# leanometer.net
KiCad netlist of a schematic drawn in EAGLE
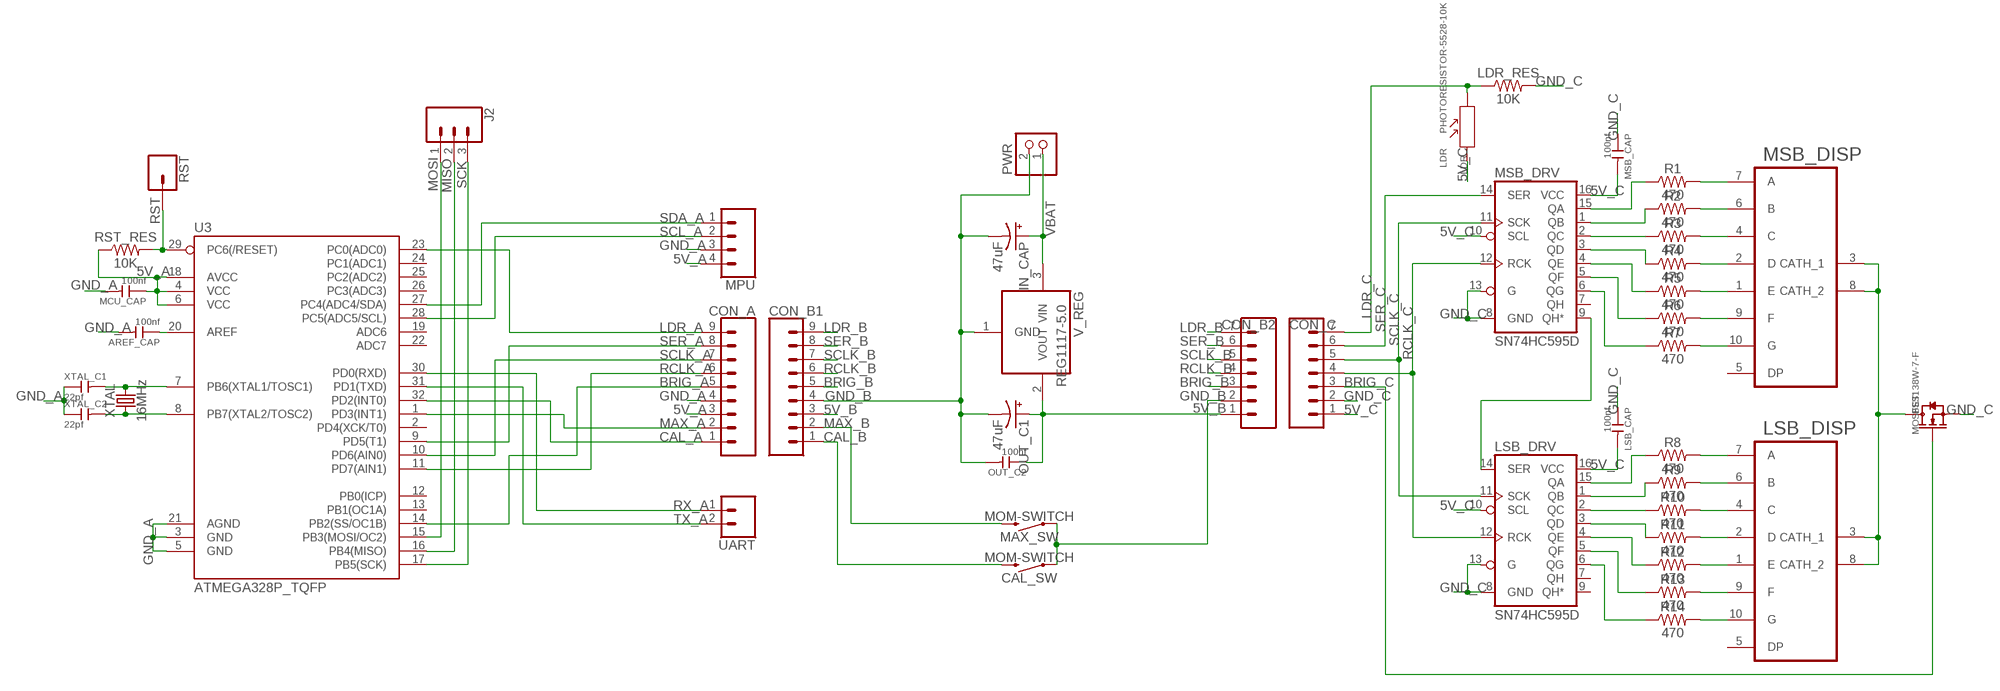
[diagram p0: schematic, sheet 1]

(export (version "E")
  (design (tool "Eeschema 10.0.6"))
  (components
    (comp (ref "AREF_CAP")
      (value "100nf")
      (footprint "eagle-import:C0805")
      (fields (field (name "MPN") "CC0805KRX7R9BB104"))
      (libsource (lib "eagle-import") (part "CERAMIC-100NF-50V-10%-X7R(0805)"))
    )
    (comp (ref "CAL_SW")
      (value "MOM-SWITCH")
      (footprint "eagle-import:TACTILE_SWITCH_PTH_6.0MM")
      (libsource (lib "eagle-import") (part "MOMENTARY-SWITCH-SPST-PTH-6.0MM"))
    )
    (comp (ref "CON_A")
      (value "CONN_09")
      (footprint "eagle-import:1X09")
      (libsource (lib "eagle-import") (part "CONN_09"))
    )
    (comp (ref "CON_B1")
      (value "CONN_09")
      (footprint "eagle-import:1X09")
      (libsource (lib "eagle-import") (part "CONN_09"))
    )
    (comp (ref "CON_B2")
      (value "CONN_07")
      (footprint "eagle-import:1X07")
      (libsource (lib "eagle-import") (part "CONN_07"))
    )
    (comp (ref "CON_C")
      (value "CONN_07")
      (footprint "eagle-import:1X07")
      (libsource (lib "eagle-import") (part "CONN_07"))
    )
    (comp (ref "IN_CAP")
      (value "47uF")
      (footprint "eagle-import:CPOL-RADIAL-2.5MM-6.5MM")
      (libsource (lib "eagle-import") (part "100UF-POLAR-RADIAL-2.5MM-25V-20%"))
    )
    (comp (ref "J2")
      (value "CONN_03")
      (footprint "eagle-import:1X03")
      (libsource (lib "eagle-import") (part "CONN_03"))
    )
    (comp (ref "LDR")
      (value "PHOTORESISTOR-5528-10K")
      (footprint "eagle-import:SNR2-3.0")
      (libsource (lib "eagle-import") (part "PHOTORESISTOR-5528-10K(2P-5.0X4.2MM)"))
    )
    (comp (ref "LDR_RES")
      (value "10K")
      (footprint "eagle-import:0805")
      (libsource (lib "eagle-import") (part "RESISTOR0805"))
    )
    (comp (ref "LSB_CAP")
      (value "100nf")
      (footprint "eagle-import:C0805")
      (fields (field (name "MPN") "CC0805KRX7R9BB104"))
      (libsource (lib "eagle-import") (part "CERAMIC-100NF-50V-10%-X7R(0805)"))
    )
    (comp (ref "LSB_DISP")
      (value "OPD-S5621LE-BW")
      (footprint "eagle-import:0.56''_LED_DISPLAY")
      (libsource (lib "eagle-import") (part "OPD-S5621LE-BW"))
    )
    (comp (ref "LSB_DRV")
      (value "SN74HC595D")
      (footprint "eagle-import:SO16")
      (libsource (lib "eagle-import") (part "74595DHC"))
    )
    (comp (ref "MAX_SW")
      (value "MOM-SWITCH")
      (footprint "eagle-import:TACTILE_SWITCH_PTH_6.0MM")
      (libsource (lib "eagle-import") (part "MOMENTARY-SWITCH-SPST-PTH-6.0MM"))
    )
    (comp (ref "MCU_CAP")
      (value "100nf")
      (footprint "eagle-import:C0805")
      (fields (field (name "MPN") "CC0805KRX7R9BB104"))
      (libsource (lib "eagle-import") (part "CERAMIC-100NF-50V-10%-X7R(0805)"))
    )
    (comp (ref "MOSFET")
      (value "BSS138W-7-F")
      (footprint "eagle-import:SOT-23")
      (libsource (lib "eagle-import") (part "SMD-MOSFET-N-CH-50V-200MA-BSS138W-7-F(SOT-23)"))
    )
    (comp (ref "MPU")
      (value "CONN_04")
      (footprint "eagle-import:1X04")
      (libsource (lib "eagle-import") (part "CONN_04"))
    )
    (comp (ref "MSB_CAP")
      (value "100nf")
      (footprint "eagle-import:C0805")
      (fields (field (name "MPN") "CC0805KRX7R9BB104"))
      (libsource (lib "eagle-import") (part "CERAMIC-100NF-50V-10%-X7R(0805)"))
    )
    (comp (ref "MSB_DISP")
      (value "OPD-S5621LE-BW")
      (footprint "eagle-import:0.56''_LED_DISPLAY")
      (libsource (lib "eagle-import") (part "OPD-S5621LE-BW"))
    )
    (comp (ref "MSB_DRV")
      (value "SN74HC595D")
      (footprint "eagle-import:SO16")
      (libsource (lib "eagle-import") (part "74595DHC"))
    )
    (comp (ref "OUT_C1")
      (value "47uF")
      (footprint "eagle-import:CPOL-RADIAL-2.5MM-6.5MM")
      (libsource (lib "eagle-import") (part "100UF-POLAR-RADIAL-2.5MM-25V-20%"))
    )
    (comp (ref "OUT_C2")
      (value "100nf")
      (footprint "eagle-import:C0805")
      (fields (field (name "MPN") "CC0805KRX7R9BB104"))
      (libsource (lib "eagle-import") (part "CERAMIC-100NF-50V-10%-X7R(0805)"))
    )
    (comp (ref "PWR")
      (value "JST_2PIN-THM-RA")
      (footprint "eagle-import:JST-PH-2-THM-RA")
      (libsource (lib "eagle-import") (part "JST_2PIN-THM-RA"))
    )
    (comp (ref "R1")
      (value "470")
      (footprint "eagle-import:0805")
      (libsource (lib "eagle-import") (part "RESISTOR0805"))
    )
    (comp (ref "R2")
      (value "470")
      (footprint "eagle-import:0805")
      (libsource (lib "eagle-import") (part "RESISTOR0805"))
    )
    (comp (ref "R3")
      (value "470")
      (footprint "eagle-import:0805")
      (libsource (lib "eagle-import") (part "RESISTOR0805"))
    )
    (comp (ref "R4")
      (value "470")
      (footprint "eagle-import:0805")
      (libsource (lib "eagle-import") (part "RESISTOR0805"))
    )
    (comp (ref "R5")
      (value "470")
      (footprint "eagle-import:0805")
      (libsource (lib "eagle-import") (part "RESISTOR0805"))
    )
    (comp (ref "R6")
      (value "470")
      (footprint "eagle-import:0805")
      (libsource (lib "eagle-import") (part "RESISTOR0805"))
    )
    (comp (ref "R7")
      (value "470")
      (footprint "eagle-import:0805")
      (libsource (lib "eagle-import") (part "RESISTOR0805"))
    )
    (comp (ref "R8")
      (value "470")
      (footprint "eagle-import:0805")
      (libsource (lib "eagle-import") (part "RESISTOR0805"))
    )
    (comp (ref "R9")
      (value "470")
      (footprint "eagle-import:0805")
      (libsource (lib "eagle-import") (part "RESISTOR0805"))
    )
    (comp (ref "R10")
      (value "470")
      (footprint "eagle-import:0805")
      (libsource (lib "eagle-import") (part "RESISTOR0805"))
    )
    (comp (ref "R11")
      (value "470")
      (footprint "eagle-import:0805")
      (libsource (lib "eagle-import") (part "RESISTOR0805"))
    )
    (comp (ref "R12")
      (value "470")
      (footprint "eagle-import:0805")
      (libsource (lib "eagle-import") (part "RESISTOR0805"))
    )
    (comp (ref "R13")
      (value "470")
      (footprint "eagle-import:0805")
      (libsource (lib "eagle-import") (part "RESISTOR0805"))
    )
    (comp (ref "R14")
      (value "470")
      (footprint "eagle-import:0805")
      (libsource (lib "eagle-import") (part "RESISTOR0805"))
    )
    (comp (ref "RST")
      (value "CONN_01")
      (footprint "eagle-import:1X01")
      (libsource (lib "eagle-import") (part "CONN_01"))
    )
    (comp (ref "RST_RES")
      (value "10K")
      (footprint "eagle-import:0805")
      (libsource (lib "eagle-import") (part "RESISTOR0805"))
    )
    (comp (ref "U3")
      (value "ATMEGA328P_TQFP")
      (footprint "eagle-import:TQFP32-08")
      (libsource (lib "eagle-import") (part "ATMEGA328P_TQFP"))
    )
    (comp (ref "UART")
      (value "CONN_02")
      (footprint "eagle-import:1X02")
      (libsource (lib "eagle-import") (part "CONN_02"))
    )
    (comp (ref "V_REG")
      (value "REG1117-5.0")
      (footprint "eagle-import:SOT223")
      (fields (field (name "MPN") "REG1117"))
      (libsource (lib "eagle-import") (part "REG1117"))
    )
    (comp (ref "XTAL")
      (value "16MHz")
      (footprint "eagle-import:HC49US")
      (libsource (lib "eagle-import") (part "CRYSTAL-16MHZPTH-HC49US"))
    )
    (comp (ref "XTAL_C1")
      (value "22pf")
      (footprint "eagle-import:C0805")
      (fields (field (name "MPN") "CC0805KRX7R9BB104"))
      (libsource (lib "eagle-import") (part "CERAMIC-100NF-50V-10%-X7R(0805)"))
    )
    (comp (ref "XTAL_C2")
      (value "22pf")
      (footprint "eagle-import:C0805")
      (fields (field (name "MPN") "CC0805KRX7R9BB104"))
      (libsource (lib "eagle-import") (part "CERAMIC-100NF-50V-10%-X7R(0805)"))
    )
  )
  (nets
    (net (code "1") (name "/5V_A") (class "Default")
      (node (ref "CON_A") (pin "3") (pinfunction "3_3") (pintype "passive"))
      (node (ref "MCU_CAP") (pin "1") (pinfunction "1_1") (pintype "passive"))
      (node (ref "MPU") (pin "4") (pinfunction "4_4") (pintype "passive"))
      (node (ref "RST_RES") (pin "1") (pinfunction "1_1") (pintype "passive"))
      (node (ref "U3") (pin "18") (pinfunction "AVCC_18") (pintype "bidirectional"))
      (node (ref "U3") (pin "4") (pinfunction "VCC_4") (pintype "bidirectional"))
      (node (ref "U3") (pin "6") (pinfunction "VCC_6") (pintype "bidirectional"))
    )
    (net (code "2") (name "/5V_B") (class "Default")
      (node (ref "CON_B1") (pin "3") (pinfunction "3_3") (pintype "passive"))
      (node (ref "CON_B2") (pin "1") (pinfunction "1_1") (pintype "passive"))
      (node (ref "OUT_C1") (pin "1") (pinfunction "+_1") (pintype "passive"))
      (node (ref "OUT_C2") (pin "1") (pinfunction "1_1") (pintype "passive"))
      (node (ref "V_REG") (pin "2") (pinfunction "VOUT_2") (pintype "output"))
    )
    (net (code "3") (name "/5V_C") (class "Default")
      (node (ref "CON_C") (pin "1") (pinfunction "1_1") (pintype "passive"))
      (node (ref "LDR") (pin "1") (pinfunction "P$1_1") (pintype "bidirectional"))
      (node (ref "LSB_CAP") (pin "2") (pinfunction "2_2") (pintype "passive"))
      (node (ref "LSB_DRV") (pin "10") (pinfunction "SCL_10") (pintype "input"))
      (node (ref "LSB_DRV") (pin "16") (pinfunction "VCC_16") (pintype "power_in"))
      (node (ref "MSB_CAP") (pin "2") (pinfunction "2_2") (pintype "passive"))
      (node (ref "MSB_DRV") (pin "10") (pinfunction "SCL_10") (pintype "input"))
      (node (ref "MSB_DRV") (pin "16") (pinfunction "VCC_16") (pintype "power_in"))
    )
    (net (code "4") (name "/BRIG_A") (class "Default")
      (node (ref "CON_A") (pin "5") (pinfunction "5_5") (pintype "passive"))
      (node (ref "U3") (pin "14") (pinfunction "PB2(SS/OC1B)_14") (pintype "bidirectional"))
    )
    (net (code "5") (name "/BRIG_B") (class "Default")
      (node (ref "CON_B1") (pin "5") (pinfunction "5_5") (pintype "passive"))
      (node (ref "CON_B2") (pin "3") (pinfunction "3_3") (pintype "passive"))
    )
    (net (code "6") (name "/BRIG_C") (class "Default")
      (node (ref "CON_C") (pin "3") (pinfunction "3_3") (pintype "passive"))
      (node (ref "MOSFET") (pin "1") (pinfunction "G_1") (pintype "passive"))
    )
    (net (code "7") (name "/CAL_A") (class "Default")
      (node (ref "CON_A") (pin "1") (pinfunction "1_1") (pintype "passive"))
      (node (ref "U3") (pin "32") (pinfunction "PD2(INT0)_32") (pintype "bidirectional"))
    )
    (net (code "8") (name "/CAL_B") (class "Default")
      (node (ref "CAL_SW") (pin "3") (pinfunction "2_3") (pintype "passive"))
      (node (ref "CON_B1") (pin "1") (pinfunction "1_1") (pintype "passive"))
    )
    (net (code "9") (name "/GND_A") (class "Default")
      (node (ref "AREF_CAP") (pin "2") (pinfunction "2_2") (pintype "passive"))
      (node (ref "CON_A") (pin "4") (pinfunction "4_4") (pintype "passive"))
      (node (ref "MCU_CAP") (pin "2") (pinfunction "2_2") (pintype "passive"))
      (node (ref "MPU") (pin "3") (pinfunction "3_3") (pintype "passive"))
      (node (ref "U3") (pin "21") (pinfunction "AGND_21") (pintype "bidirectional"))
      (node (ref "U3") (pin "3") (pinfunction "GND_3") (pintype "bidirectional"))
      (node (ref "U3") (pin "5") (pinfunction "GND_5") (pintype "bidirectional"))
      (node (ref "XTAL_C1") (pin "1") (pinfunction "1_1") (pintype "passive"))
      (node (ref "XTAL_C2") (pin "1") (pinfunction "1_1") (pintype "passive"))
    )
    (net (code "10") (name "/GND_B") (class "Default")
      (node (ref "CAL_SW") (pin "1") (pinfunction "1_1") (pintype "passive"))
      (node (ref "CON_B1") (pin "4") (pinfunction "4_4") (pintype "passive"))
      (node (ref "CON_B2") (pin "2") (pinfunction "2_2") (pintype "passive"))
      (node (ref "IN_CAP") (pin "2") (pinfunction "-_2") (pintype "passive"))
      (node (ref "MAX_SW") (pin "1") (pinfunction "1_1") (pintype "passive"))
      (node (ref "OUT_C1") (pin "2") (pinfunction "-_2") (pintype "passive"))
      (node (ref "OUT_C2") (pin "2") (pinfunction "2_2") (pintype "passive"))
      (node (ref "PWR") (pin "2") (pinfunction "1_2") (pintype "passive"))
      (node (ref "V_REG") (pin "1") (pinfunction "GND_1") (pintype "power_in"))
    )
    (net (code "11") (name "/GND_C") (class "Default")
      (node (ref "CON_C") (pin "2") (pinfunction "2_2") (pintype "passive"))
      (node (ref "LDR_RES") (pin "2") (pinfunction "2_2") (pintype "passive"))
      (node (ref "LSB_CAP") (pin "1") (pinfunction "1_1") (pintype "passive"))
      (node (ref "LSB_DRV") (pin "13") (pinfunction "G_13") (pintype "input"))
      (node (ref "LSB_DRV") (pin "8") (pinfunction "GND_8") (pintype "power_in"))
      (node (ref "MOSFET") (pin "2") (pinfunction "S_2") (pintype "passive"))
      (node (ref "MSB_CAP") (pin "1") (pinfunction "1_1") (pintype "passive"))
      (node (ref "MSB_DRV") (pin "13") (pinfunction "G_13") (pintype "input"))
      (node (ref "MSB_DRV") (pin "8") (pinfunction "GND_8") (pintype "power_in"))
    )
    (net (code "12") (name "/LDR_A") (class "Default")
      (node (ref "CON_A") (pin "9") (pinfunction "9_9") (pintype "passive"))
      (node (ref "U3") (pin "23") (pinfunction "PC0(ADC0)_23") (pintype "bidirectional"))
    )
    (net (code "13") (name "/LDR_B") (class "Default")
      (node (ref "CON_B1") (pin "9") (pinfunction "9_9") (pintype "passive"))
      (node (ref "CON_B2") (pin "7") (pinfunction "7_7") (pintype "passive"))
    )
    (net (code "14") (name "/LDR_C") (class "Default")
      (node (ref "CON_C") (pin "7") (pinfunction "7_7") (pintype "passive"))
      (node (ref "LDR") (pin "2") (pinfunction "P$2_2") (pintype "bidirectional"))
      (node (ref "LDR_RES") (pin "1") (pinfunction "1_1") (pintype "passive"))
    )
    (net (code "15") (name "/MAX_A") (class "Default")
      (node (ref "CON_A") (pin "2") (pinfunction "2_2") (pintype "passive"))
      (node (ref "U3") (pin "1") (pinfunction "PD3(INT1)_1") (pintype "bidirectional"))
    )
    (net (code "16") (name "/MAX_B") (class "Default")
      (node (ref "CON_B1") (pin "2") (pinfunction "2_2") (pintype "passive"))
      (node (ref "MAX_SW") (pin "3") (pinfunction "2_3") (pintype "passive"))
    )
    (net (code "17") (name "/MISO") (class "Default")
      (node (ref "J2") (pin "2") (pinfunction "2_2") (pintype "passive"))
      (node (ref "U3") (pin "16") (pinfunction "PB4(MISO)_16") (pintype "bidirectional"))
    )
    (net (code "18") (name "/MOSI") (class "Default")
      (node (ref "J2") (pin "1") (pinfunction "1_1") (pintype "passive"))
      (node (ref "U3") (pin "15") (pinfunction "PB3(MOSI/OC2)_15") (pintype "bidirectional"))
    )
    (net (code "19") (name "/RCLK_A") (class "Default")
      (node (ref "CON_A") (pin "6") (pinfunction "6_6") (pintype "passive"))
      (node (ref "U3") (pin "11") (pinfunction "PD7(AIN1)_11") (pintype "bidirectional"))
    )
    (net (code "20") (name "/RCLK_B") (class "Default")
      (node (ref "CON_B1") (pin "6") (pinfunction "6_6") (pintype "passive"))
      (node (ref "CON_B2") (pin "4") (pinfunction "4_4") (pintype "passive"))
    )
    (net (code "21") (name "/RCLK_C") (class "Default")
      (node (ref "CON_C") (pin "4") (pinfunction "4_4") (pintype "passive"))
      (node (ref "LSB_DRV") (pin "12") (pinfunction "RCK_12") (pintype "input"))
      (node (ref "MSB_DRV") (pin "12") (pinfunction "RCK_12") (pintype "input"))
    )
    (net (code "22") (name "/RST") (class "Default")
      (node (ref "RST") (pin "1") (pinfunction "1_1") (pintype "passive"))
      (node (ref "RST_RES") (pin "2") (pinfunction "2_2") (pintype "passive"))
      (node (ref "U3") (pin "29") (pinfunction "PC6(/RESET)_29") (pintype "bidirectional"))
    )
    (net (code "23") (name "/RX_A") (class "Default")
      (node (ref "U3") (pin "30") (pinfunction "PD0(RXD)_30") (pintype "bidirectional"))
      (node (ref "UART") (pin "1") (pinfunction "1_1") (pintype "passive"))
    )
    (net (code "24") (name "/SCK") (class "Default")
      (node (ref "J2") (pin "3") (pinfunction "3_3") (pintype "passive"))
      (node (ref "U3") (pin "17") (pinfunction "PB5(SCK)_17") (pintype "bidirectional"))
    )
    (net (code "25") (name "/SCLK_A") (class "Default")
      (node (ref "CON_A") (pin "7") (pinfunction "7_7") (pintype "passive"))
      (node (ref "U3") (pin "10") (pinfunction "PD6(AIN0)_10") (pintype "bidirectional"))
    )
    (net (code "26") (name "/SCLK_B") (class "Default")
      (node (ref "CON_B1") (pin "7") (pinfunction "7_7") (pintype "passive"))
      (node (ref "CON_B2") (pin "5") (pinfunction "5_5") (pintype "passive"))
    )
    (net (code "27") (name "/SCLK_C") (class "Default")
      (node (ref "CON_C") (pin "5") (pinfunction "5_5") (pintype "passive"))
      (node (ref "LSB_DRV") (pin "11") (pinfunction "SCK_11") (pintype "input"))
      (node (ref "MSB_DRV") (pin "11") (pinfunction "SCK_11") (pintype "input"))
    )
    (net (code "28") (name "/SCL_A") (class "Default")
      (node (ref "MPU") (pin "2") (pinfunction "2_2") (pintype "passive"))
      (node (ref "U3") (pin "28") (pinfunction "PC5(ADC5/SCL)_28") (pintype "bidirectional"))
    )
    (net (code "29") (name "/SDA_A") (class "Default")
      (node (ref "MPU") (pin "1") (pinfunction "1_1") (pintype "passive"))
      (node (ref "U3") (pin "27") (pinfunction "PC4(ADC4/SDA)_27") (pintype "bidirectional"))
    )
    (net (code "30") (name "/SER_A") (class "Default")
      (node (ref "CON_A") (pin "8") (pinfunction "8_8") (pintype "passive"))
      (node (ref "U3") (pin "9") (pinfunction "PD5(T1)_9") (pintype "bidirectional"))
    )
    (net (code "31") (name "/SER_B") (class "Default")
      (node (ref "CON_B1") (pin "8") (pinfunction "8_8") (pintype "passive"))
      (node (ref "CON_B2") (pin "6") (pinfunction "6_6") (pintype "passive"))
    )
    (net (code "32") (name "/SER_C") (class "Default")
      (node (ref "CON_C") (pin "6") (pinfunction "6_6") (pintype "passive"))
      (node (ref "MSB_DRV") (pin "14") (pinfunction "SER_14") (pintype "input"))
    )
    (net (code "33") (name "/TX_A") (class "Default")
      (node (ref "U3") (pin "31") (pinfunction "PD1(TXD)_31") (pintype "bidirectional"))
      (node (ref "UART") (pin "2") (pinfunction "2_2") (pintype "passive"))
    )
    (net (code "34") (name "/VBAT") (class "Default")
      (node (ref "IN_CAP") (pin "1") (pinfunction "+_1") (pintype "passive"))
      (node (ref "PWR") (pin "1") (pinfunction "2_1") (pintype "passive"))
      (node (ref "V_REG") (pin "3") (pinfunction "VIN_3") (pintype "input"))
    )
    (net (code "35") (name "Net-(LSB_DISP-A)") (class "Default")
      (node (ref "LSB_DISP") (pin "7") (pinfunction "A_7") (pintype "bidirectional"))
      (node (ref "R8") (pin "2") (pinfunction "2_2") (pintype "passive"))
    )
    (net (code "36") (name "Net-(LSB_DISP-B)") (class "Default")
      (node (ref "LSB_DISP") (pin "6") (pinfunction "B_6") (pintype "bidirectional"))
      (node (ref "R9") (pin "2") (pinfunction "2_2") (pintype "passive"))
    )
    (net (code "37") (name "Net-(LSB_DISP-C)") (class "Default")
      (node (ref "LSB_DISP") (pin "4") (pinfunction "C_4") (pintype "bidirectional"))
      (node (ref "R10") (pin "2") (pinfunction "2_2") (pintype "passive"))
    )
    (net (code "38") (name "Net-(LSB_DISP-CATH_1)") (class "Default")
      (node (ref "LSB_DISP") (pin "3") (pinfunction "CATH_1_3") (pintype "bidirectional"))
      (node (ref "LSB_DISP") (pin "8") (pinfunction "CATH_2_8") (pintype "bidirectional"))
      (node (ref "MOSFET") (pin "3") (pinfunction "D_3") (pintype "passive"))
      (node (ref "MSB_DISP") (pin "3") (pinfunction "CATH_1_3") (pintype "bidirectional"))
      (node (ref "MSB_DISP") (pin "8") (pinfunction "CATH_2_8") (pintype "bidirectional"))
    )
    (net (code "39") (name "Net-(LSB_DISP-D)") (class "Default")
      (node (ref "LSB_DISP") (pin "2") (pinfunction "D_2") (pintype "bidirectional"))
      (node (ref "R11") (pin "2") (pinfunction "2_2") (pintype "passive"))
    )
    (net (code "40") (name "Net-(LSB_DISP-E)") (class "Default")
      (node (ref "LSB_DISP") (pin "1") (pinfunction "E_1") (pintype "bidirectional"))
      (node (ref "R12") (pin "2") (pinfunction "2_2") (pintype "passive"))
    )
    (net (code "41") (name "Net-(LSB_DISP-F)") (class "Default")
      (node (ref "LSB_DISP") (pin "9") (pinfunction "F_9") (pintype "bidirectional"))
      (node (ref "R13") (pin "2") (pinfunction "2_2") (pintype "passive"))
    )
    (net (code "42") (name "Net-(LSB_DISP-G)") (class "Default")
      (node (ref "LSB_DISP") (pin "10") (pinfunction "G_10") (pintype "bidirectional"))
      (node (ref "R14") (pin "2") (pinfunction "2_2") (pintype "passive"))
    )
    (net (code "43") (name "Net-(LSB_DRV-QA)") (class "Default")
      (node (ref "LSB_DRV") (pin "15") (pinfunction "QA_15") (pintype "tri_state"))
      (node (ref "R8") (pin "1") (pinfunction "1_1") (pintype "passive"))
    )
    (net (code "44") (name "Net-(LSB_DRV-QB)") (class "Default")
      (node (ref "LSB_DRV") (pin "1") (pinfunction "QB_1") (pintype "tri_state"))
      (node (ref "R9") (pin "1") (pinfunction "1_1") (pintype "passive"))
    )
    (net (code "45") (name "Net-(LSB_DRV-QC)") (class "Default")
      (node (ref "LSB_DRV") (pin "2") (pinfunction "QC_2") (pintype "tri_state"))
      (node (ref "R10") (pin "1") (pinfunction "1_1") (pintype "passive"))
    )
    (net (code "46") (name "Net-(LSB_DRV-QD)") (class "Default")
      (node (ref "LSB_DRV") (pin "3") (pinfunction "QD_3") (pintype "tri_state"))
      (node (ref "R11") (pin "1") (pinfunction "1_1") (pintype "passive"))
    )
    (net (code "47") (name "Net-(LSB_DRV-QE)") (class "Default")
      (node (ref "LSB_DRV") (pin "4") (pinfunction "QE_4") (pintype "tri_state"))
      (node (ref "R12") (pin "1") (pinfunction "1_1") (pintype "passive"))
    )
    (net (code "48") (name "Net-(LSB_DRV-QF)") (class "Default")
      (node (ref "LSB_DRV") (pin "5") (pinfunction "QF_5") (pintype "tri_state"))
      (node (ref "R13") (pin "1") (pinfunction "1_1") (pintype "passive"))
    )
    (net (code "49") (name "Net-(LSB_DRV-QG)") (class "Default")
      (node (ref "LSB_DRV") (pin "6") (pinfunction "QG_6") (pintype "tri_state"))
      (node (ref "R14") (pin "1") (pinfunction "1_1") (pintype "passive"))
    )
    (net (code "50") (name "Net-(LSB_DRV-SER)") (class "Default")
      (node (ref "LSB_DRV") (pin "14") (pinfunction "SER_14") (pintype "input"))
      (node (ref "MSB_DRV") (pin "9") (pinfunction "QH*_9") (pintype "tri_state"))
    )
    (net (code "51") (name "Net-(MSB_DISP-A)") (class "Default")
      (node (ref "MSB_DISP") (pin "7") (pinfunction "A_7") (pintype "bidirectional"))
      (node (ref "R1") (pin "2") (pinfunction "2_2") (pintype "passive"))
    )
    (net (code "52") (name "Net-(MSB_DISP-B)") (class "Default")
      (node (ref "MSB_DISP") (pin "6") (pinfunction "B_6") (pintype "bidirectional"))
      (node (ref "R2") (pin "2") (pinfunction "2_2") (pintype "passive"))
    )
    (net (code "53") (name "Net-(MSB_DISP-C)") (class "Default")
      (node (ref "MSB_DISP") (pin "4") (pinfunction "C_4") (pintype "bidirectional"))
      (node (ref "R3") (pin "2") (pinfunction "2_2") (pintype "passive"))
    )
    (net (code "54") (name "Net-(MSB_DISP-D)") (class "Default")
      (node (ref "MSB_DISP") (pin "2") (pinfunction "D_2") (pintype "bidirectional"))
      (node (ref "R4") (pin "2") (pinfunction "2_2") (pintype "passive"))
    )
    (net (code "55") (name "Net-(MSB_DISP-E)") (class "Default")
      (node (ref "MSB_DISP") (pin "1") (pinfunction "E_1") (pintype "bidirectional"))
      (node (ref "R5") (pin "2") (pinfunction "2_2") (pintype "passive"))
    )
    (net (code "56") (name "Net-(MSB_DISP-F)") (class "Default")
      (node (ref "MSB_DISP") (pin "9") (pinfunction "F_9") (pintype "bidirectional"))
      (node (ref "R6") (pin "2") (pinfunction "2_2") (pintype "passive"))
    )
    (net (code "57") (name "Net-(MSB_DISP-G)") (class "Default")
      (node (ref "MSB_DISP") (pin "10") (pinfunction "G_10") (pintype "bidirectional"))
      (node (ref "R7") (pin "2") (pinfunction "2_2") (pintype "passive"))
    )
    (net (code "58") (name "Net-(MSB_DRV-QA)") (class "Default")
      (node (ref "MSB_DRV") (pin "15") (pinfunction "QA_15") (pintype "tri_state"))
      (node (ref "R1") (pin "1") (pinfunction "1_1") (pintype "passive"))
    )
    (net (code "59") (name "Net-(MSB_DRV-QB)") (class "Default")
      (node (ref "MSB_DRV") (pin "1") (pinfunction "QB_1") (pintype "tri_state"))
      (node (ref "R2") (pin "1") (pinfunction "1_1") (pintype "passive"))
    )
    (net (code "60") (name "Net-(MSB_DRV-QC)") (class "Default")
      (node (ref "MSB_DRV") (pin "2") (pinfunction "QC_2") (pintype "tri_state"))
      (node (ref "R3") (pin "1") (pinfunction "1_1") (pintype "passive"))
    )
    (net (code "61") (name "Net-(MSB_DRV-QD)") (class "Default")
      (node (ref "MSB_DRV") (pin "3") (pinfunction "QD_3") (pintype "tri_state"))
      (node (ref "R4") (pin "1") (pinfunction "1_1") (pintype "passive"))
    )
    (net (code "62") (name "Net-(MSB_DRV-QE)") (class "Default")
      (node (ref "MSB_DRV") (pin "4") (pinfunction "QE_4") (pintype "tri_state"))
      (node (ref "R5") (pin "1") (pinfunction "1_1") (pintype "passive"))
    )
    (net (code "63") (name "Net-(MSB_DRV-QF)") (class "Default")
      (node (ref "MSB_DRV") (pin "5") (pinfunction "QF_5") (pintype "tri_state"))
      (node (ref "R6") (pin "1") (pinfunction "1_1") (pintype "passive"))
    )
    (net (code "64") (name "Net-(MSB_DRV-QG)") (class "Default")
      (node (ref "MSB_DRV") (pin "6") (pinfunction "QG_6") (pintype "tri_state"))
      (node (ref "R7") (pin "1") (pinfunction "1_1") (pintype "passive"))
    )
    (net (code "65") (name "Net-(U3-AREF)") (class "Default")
      (node (ref "AREF_CAP") (pin "1") (pinfunction "1_1") (pintype "passive"))
      (node (ref "U3") (pin "20") (pinfunction "AREF_20") (pintype "bidirectional"))
    )
    (net (code "66") (name "Net-(U3-PB6(XTAL1{slash}TOSC1))") (class "Default")
      (node (ref "U3") (pin "7") (pinfunction "PB6(XTAL1/TOSC1)_7") (pintype "bidirectional"))
      (node (ref "XTAL") (pin "2") (pinfunction "2_2") (pintype "passive"))
      (node (ref "XTAL_C1") (pin "2") (pinfunction "2_2") (pintype "passive"))
    )
    (net (code "67") (name "Net-(U3-PB7(XTAL2{slash}TOSC2))") (class "Default")
      (node (ref "U3") (pin "8") (pinfunction "PB7(XTAL2/TOSC2)_8") (pintype "bidirectional"))
      (node (ref "XTAL") (pin "1") (pinfunction "1_1") (pintype "passive"))
      (node (ref "XTAL_C2") (pin "2") (pinfunction "2_2") (pintype "passive"))
    )
    (net (code "68") (name "unconnected-(LSB_DISP-DP-Pad5)") (class "Default")
      (node (ref "LSB_DISP") (pin "5") (pinfunction "DP_5") (pintype "bidirectional"))
    )
    (net (code "69") (name "unconnected-(LSB_DRV-QH*-Pad9)") (class "Default")
      (node (ref "LSB_DRV") (pin "9") (pinfunction "QH*_9") (pintype "tri_state"))
    )
    (net (code "70") (name "unconnected-(LSB_DRV-QH-Pad7)") (class "Default")
      (node (ref "LSB_DRV") (pin "7") (pinfunction "QH_7") (pintype "tri_state"))
    )
    (net (code "71") (name "unconnected-(MSB_DISP-DP-Pad5)") (class "Default")
      (node (ref "MSB_DISP") (pin "5") (pinfunction "DP_5") (pintype "bidirectional"))
    )
    (net (code "72") (name "unconnected-(MSB_DRV-QH-Pad7)") (class "Default")
      (node (ref "MSB_DRV") (pin "7") (pinfunction "QH_7") (pintype "tri_state"))
    )
    (net (code "73") (name "unconnected-(U3-ADC6-Pad19)") (class "Default")
      (node (ref "U3") (pin "19") (pinfunction "ADC6_19") (pintype "bidirectional"))
    )
    (net (code "74") (name "unconnected-(U3-ADC7-Pad22)") (class "Default")
      (node (ref "U3") (pin "22") (pinfunction "ADC7_22") (pintype "bidirectional"))
    )
    (net (code "75") (name "unconnected-(U3-PB0(ICP)-Pad12)") (class "Default")
      (node (ref "U3") (pin "12") (pinfunction "PB0(ICP)_12") (pintype "bidirectional"))
    )
    (net (code "76") (name "unconnected-(U3-PB1(OC1A)-Pad13)") (class "Default")
      (node (ref "U3") (pin "13") (pinfunction "PB1(OC1A)_13") (pintype "bidirectional"))
    )
    (net (code "77") (name "unconnected-(U3-PC1(ADC1)-Pad24)") (class "Default")
      (node (ref "U3") (pin "24") (pinfunction "PC1(ADC1)_24") (pintype "bidirectional"))
    )
    (net (code "78") (name "unconnected-(U3-PC2(ADC2)-Pad25)") (class "Default")
      (node (ref "U3") (pin "25") (pinfunction "PC2(ADC2)_25") (pintype "bidirectional"))
    )
    (net (code "79") (name "unconnected-(U3-PC3(ADC3)-Pad26)") (class "Default")
      (node (ref "U3") (pin "26") (pinfunction "PC3(ADC3)_26") (pintype "bidirectional"))
    )
    (net (code "80") (name "unconnected-(U3-PD4(XCK{slash}T0)-Pad2)") (class "Default")
      (node (ref "U3") (pin "2") (pinfunction "PD4(XCK/T0)_2") (pintype "bidirectional"))
    )
  )
)
